# STice.net
KiCad netlist of a schematic drawn in Altium Designer
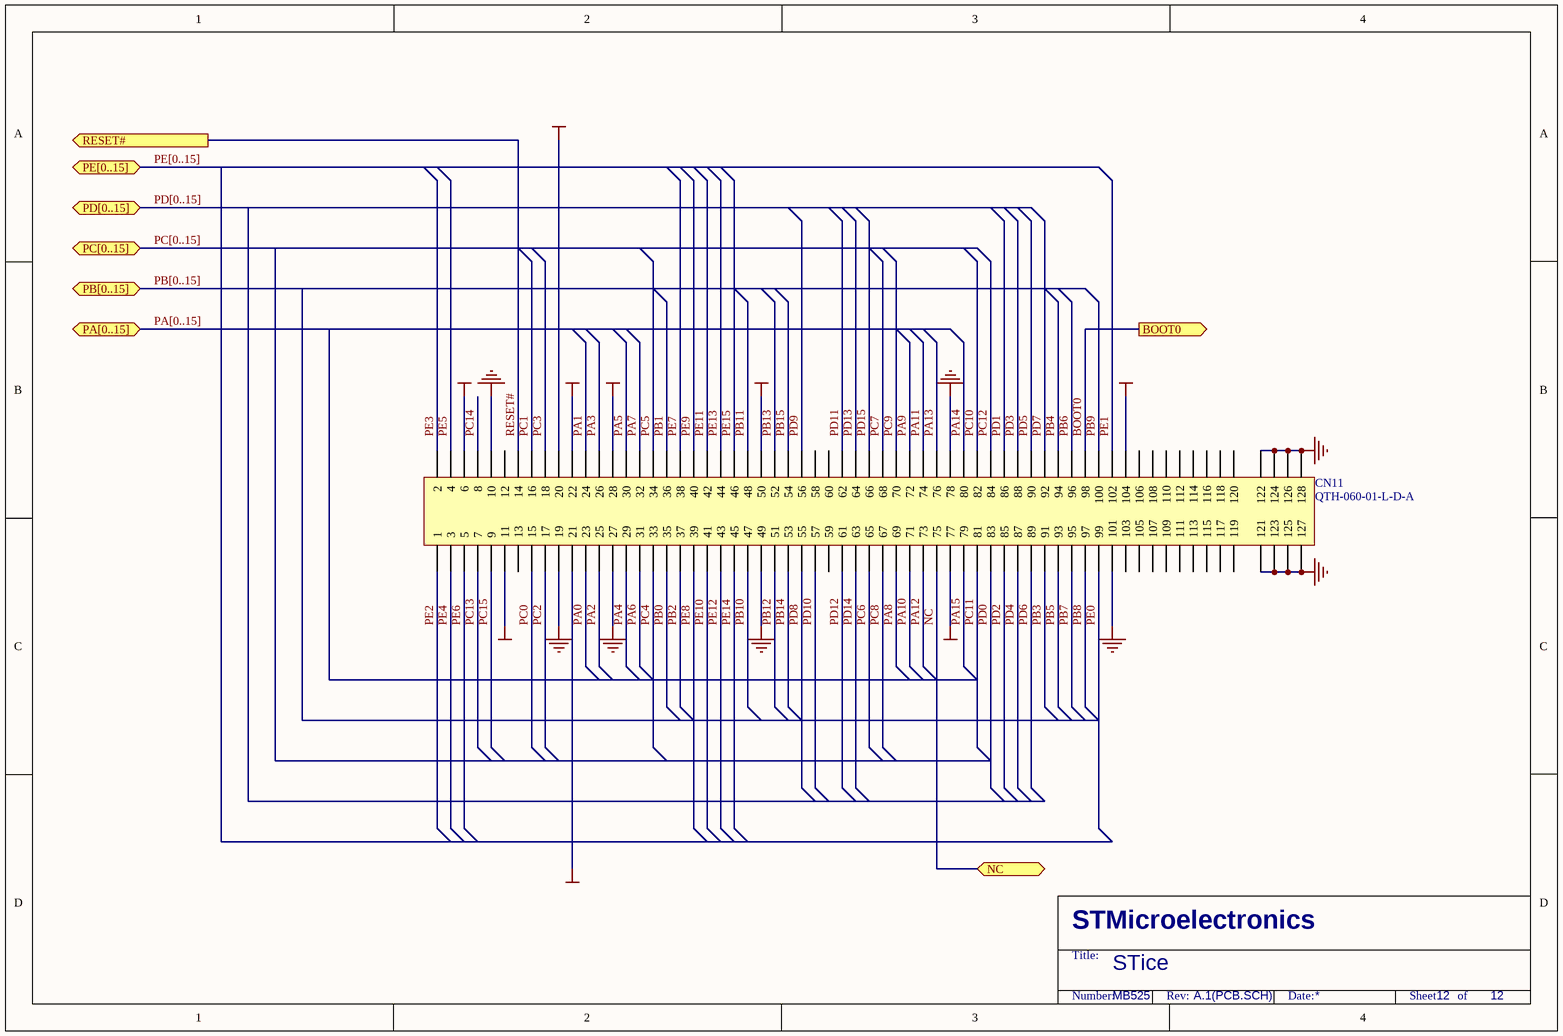
[diagram p0: STice.SchDoc]

(export (version "E")
  (design (tool "Eeschema 10.0.6"))
  (components
    (comp (ref "CN11")
      (value "QTH-060-01-L-D-A")
      (footprint "QTH-060-01-L-D-A")
      (libsource (lib "MB525") (part "QTH-060-01-L-D-A"))
    )
  )
  (nets
    (net (code "1") (name "/BOOT0") (class "Default")
      (node (ref "CN11") (pin "98") (pinfunction "98_98") (pintype "passive"))
    )
    (net (code "2") (name "/NC") (class "Default")
      (node (ref "CN11") (pin "75") (pinfunction "75_75") (pintype "passive"))
    )
    (net (code "3") (name "/PA0") (class "Default")
      (node (ref "CN11") (pin "23") (pinfunction "23_23") (pintype "passive"))
    )
    (net (code "4") (name "/PA1") (class "Default")
      (node (ref "CN11") (pin "24") (pinfunction "24_24") (pintype "passive"))
    )
    (net (code "5") (name "/PA2") (class "Default")
      (node (ref "CN11") (pin "25") (pinfunction "25_25") (pintype "passive"))
    )
    (net (code "6") (name "/PA3") (class "Default")
      (node (ref "CN11") (pin "26") (pinfunction "26_26") (pintype "passive"))
    )
    (net (code "7") (name "/PA4") (class "Default")
      (node (ref "CN11") (pin "29") (pinfunction "29_29") (pintype "passive"))
    )
    (net (code "8") (name "/PA5") (class "Default")
      (node (ref "CN11") (pin "30") (pinfunction "30_30") (pintype "passive"))
    )
    (net (code "9") (name "/PA6") (class "Default")
      (node (ref "CN11") (pin "31") (pinfunction "31_31") (pintype "passive"))
    )
    (net (code "10") (name "/PA7") (class "Default")
      (node (ref "CN11") (pin "32") (pinfunction "32_32") (pintype "passive"))
    )
    (net (code "11") (name "/PA8") (class "Default")
      (node (ref "CN11") (pin "69") (pinfunction "69_69") (pintype "passive"))
    )
    (net (code "12") (name "/PA9") (class "Default")
      (node (ref "CN11") (pin "72") (pinfunction "72_72") (pintype "passive"))
    )
    (net (code "13") (name "/PA10") (class "Default")
      (node (ref "CN11") (pin "71") (pinfunction "71_71") (pintype "passive"))
    )
    (net (code "14") (name "/PA11") (class "Default")
      (node (ref "CN11") (pin "74") (pinfunction "74_74") (pintype "passive"))
    )
    (net (code "15") (name "/PA12") (class "Default")
      (node (ref "CN11") (pin "73") (pinfunction "73_73") (pintype "passive"))
    )
    (net (code "16") (name "/PA13") (class "Default")
      (node (ref "CN11") (pin "76") (pinfunction "76_76") (pintype "passive"))
    )
    (net (code "17") (name "/PA14") (class "Default")
      (node (ref "CN11") (pin "80") (pinfunction "80_80") (pintype "passive"))
    )
    (net (code "18") (name "/PA15") (class "Default")
      (node (ref "CN11") (pin "79") (pinfunction "79_79") (pintype "passive"))
    )
    (net (code "20") (name "/PB0") (class "Default")
      (node (ref "CN11") (pin "35") (pinfunction "35_35") (pintype "passive"))
    )
    (net (code "21") (name "/PB1") (class "Default")
      (node (ref "CN11") (pin "36") (pinfunction "36_36") (pintype "passive"))
    )
    (net (code "22") (name "/PB2") (class "Default")
      (node (ref "CN11") (pin "37") (pinfunction "37_37") (pintype "passive"))
    )
    (net (code "23") (name "/PB3") (class "Default")
      (node (ref "CN11") (pin "91") (pinfunction "91_91") (pintype "passive"))
    )
    (net (code "24") (name "/PB4") (class "Default")
      (node (ref "CN11") (pin "94") (pinfunction "94_94") (pintype "passive"))
    )
    (net (code "25") (name "/PB5") (class "Default")
      (node (ref "CN11") (pin "93") (pinfunction "93_93") (pintype "passive"))
    )
    (net (code "26") (name "/PB6") (class "Default")
      (node (ref "CN11") (pin "96") (pinfunction "96_96") (pintype "passive"))
    )
    (net (code "27") (name "/PB7") (class "Default")
      (node (ref "CN11") (pin "95") (pinfunction "95_95") (pintype "passive"))
    )
    (net (code "28") (name "/PB8") (class "Default")
      (node (ref "CN11") (pin "97") (pinfunction "97_97") (pintype "passive"))
    )
    (net (code "29") (name "/PB9") (class "Default")
      (node (ref "CN11") (pin "100") (pinfunction "100_100") (pintype "passive"))
    )
    (net (code "30") (name "/PB10") (class "Default")
      (node (ref "CN11") (pin "47") (pinfunction "47_47") (pintype "passive"))
    )
    (net (code "31") (name "/PB11") (class "Default")
      (node (ref "CN11") (pin "48") (pinfunction "48_48") (pintype "passive"))
    )
    (net (code "32") (name "/PB12") (class "Default")
      (node (ref "CN11") (pin "51") (pinfunction "51_51") (pintype "passive"))
    )
    (net (code "33") (name "/PB13") (class "Default")
      (node (ref "CN11") (pin "52") (pinfunction "52_52") (pintype "passive"))
    )
    (net (code "34") (name "/PB14") (class "Default")
      (node (ref "CN11") (pin "53") (pinfunction "53_53") (pintype "passive"))
    )
    (net (code "35") (name "/PB15") (class "Default")
      (node (ref "CN11") (pin "54") (pinfunction "54_54") (pintype "passive"))
    )
    (net (code "37") (name "/PC0") (class "Default")
      (node (ref "CN11") (pin "15") (pinfunction "15_15") (pintype "passive"))
    )
    (net (code "38") (name "/PC1") (class "Default")
      (node (ref "CN11") (pin "16") (pinfunction "16_16") (pintype "passive"))
    )
    (net (code "39") (name "/PC2") (class "Default")
      (node (ref "CN11") (pin "17") (pinfunction "17_17") (pintype "passive"))
    )
    (net (code "40") (name "/PC3") (class "Default")
      (node (ref "CN11") (pin "18") (pinfunction "18_18") (pintype "passive"))
    )
    (net (code "41") (name "/PC4") (class "Default")
      (node (ref "CN11") (pin "33") (pinfunction "33_33") (pintype "passive"))
    )
    (net (code "42") (name "/PC5") (class "Default")
      (node (ref "CN11") (pin "34") (pinfunction "34_34") (pintype "passive"))
    )
    (net (code "43") (name "/PC6") (class "Default")
      (node (ref "CN11") (pin "65") (pinfunction "65_65") (pintype "passive"))
    )
    (net (code "44") (name "/PC7") (class "Default")
      (node (ref "CN11") (pin "68") (pinfunction "68_68") (pintype "passive"))
    )
    (net (code "45") (name "/PC8") (class "Default")
      (node (ref "CN11") (pin "67") (pinfunction "67_67") (pintype "passive"))
    )
    (net (code "46") (name "/PC9") (class "Default")
      (node (ref "CN11") (pin "70") (pinfunction "70_70") (pintype "passive"))
    )
    (net (code "47") (name "/PC10") (class "Default")
      (node (ref "CN11") (pin "82") (pinfunction "82_82") (pintype "passive"))
    )
    (net (code "48") (name "/PC11") (class "Default")
      (node (ref "CN11") (pin "81") (pinfunction "81_81") (pintype "passive"))
    )
    (net (code "49") (name "/PC12") (class "Default")
      (node (ref "CN11") (pin "84") (pinfunction "84_84") (pintype "passive"))
    )
    (net (code "50") (name "/PC13") (class "Default")
      (node (ref "CN11") (pin "7") (pinfunction "7_7") (pintype "passive"))
    )
    (net (code "51") (name "/PC14") (class "Default")
      (node (ref "CN11") (pin "8") (pinfunction "8_8") (pintype "passive"))
    )
    (net (code "52") (name "/PC15") (class "Default")
      (node (ref "CN11") (pin "9") (pinfunction "9_9") (pintype "passive"))
    )
    (net (code "54") (name "/PD0") (class "Default")
      (node (ref "CN11") (pin "83") (pinfunction "83_83") (pintype "passive"))
    )
    (net (code "55") (name "/PD1") (class "Default")
      (node (ref "CN11") (pin "86") (pinfunction "86_86") (pintype "passive"))
    )
    (net (code "56") (name "/PD2") (class "Default")
      (node (ref "CN11") (pin "85") (pinfunction "85_85") (pintype "passive"))
    )
    (net (code "57") (name "/PD3") (class "Default")
      (node (ref "CN11") (pin "88") (pinfunction "88_88") (pintype "passive"))
    )
    (net (code "58") (name "/PD4") (class "Default")
      (node (ref "CN11") (pin "87") (pinfunction "87_87") (pintype "passive"))
    )
    (net (code "59") (name "/PD5") (class "Default")
      (node (ref "CN11") (pin "90") (pinfunction "90_90") (pintype "passive"))
    )
    (net (code "60") (name "/PD6") (class "Default")
      (node (ref "CN11") (pin "89") (pinfunction "89_89") (pintype "passive"))
    )
    (net (code "61") (name "/PD7") (class "Default")
      (node (ref "CN11") (pin "92") (pinfunction "92_92") (pintype "passive"))
    )
    (net (code "62") (name "/PD8") (class "Default")
      (node (ref "CN11") (pin "55") (pinfunction "55_55") (pintype "passive"))
    )
    (net (code "63") (name "/PD9") (class "Default")
      (node (ref "CN11") (pin "56") (pinfunction "56_56") (pintype "passive"))
    )
    (net (code "64") (name "/PD10") (class "Default")
      (node (ref "CN11") (pin "57") (pinfunction "57_57") (pintype "passive"))
    )
    (net (code "65") (name "/PD11") (class "Default")
      (node (ref "CN11") (pin "62") (pinfunction "62_62") (pintype "passive"))
    )
    (net (code "66") (name "/PD12") (class "Default")
      (node (ref "CN11") (pin "61") (pinfunction "61_61") (pintype "passive"))
    )
    (net (code "67") (name "/PD13") (class "Default")
      (node (ref "CN11") (pin "64") (pinfunction "64_64") (pintype "passive"))
    )
    (net (code "68") (name "/PD14") (class "Default")
      (node (ref "CN11") (pin "63") (pinfunction "63_63") (pintype "passive"))
    )
    (net (code "69") (name "/PD15") (class "Default")
      (node (ref "CN11") (pin "66") (pinfunction "66_66") (pintype "passive"))
    )
    (net (code "71") (name "/PE0") (class "Default")
      (node (ref "CN11") (pin "99") (pinfunction "99_99") (pintype "passive"))
    )
    (net (code "72") (name "/PE1") (class "Default")
      (node (ref "CN11") (pin "102") (pinfunction "102_102") (pintype "passive"))
    )
    (net (code "73") (name "/PE2") (class "Default")
      (node (ref "CN11") (pin "1") (pinfunction "1_1") (pintype "passive"))
    )
    (net (code "74") (name "/PE3") (class "Default")
      (node (ref "CN11") (pin "2") (pinfunction "2_2") (pintype "passive"))
    )
    (net (code "75") (name "/PE4") (class "Default")
      (node (ref "CN11") (pin "3") (pinfunction "3_3") (pintype "passive"))
    )
    (net (code "76") (name "/PE5") (class "Default")
      (node (ref "CN11") (pin "4") (pinfunction "4_4") (pintype "passive"))
    )
    (net (code "77") (name "/PE6") (class "Default")
      (node (ref "CN11") (pin "5") (pinfunction "5_5") (pintype "passive"))
    )
    (net (code "78") (name "/PE7") (class "Default")
      (node (ref "CN11") (pin "38") (pinfunction "38_38") (pintype "passive"))
    )
    (net (code "79") (name "/PE8") (class "Default")
      (node (ref "CN11") (pin "39") (pinfunction "39_39") (pintype "passive"))
    )
    (net (code "80") (name "/PE9") (class "Default")
      (node (ref "CN11") (pin "40") (pinfunction "40_40") (pintype "passive"))
    )
    (net (code "81") (name "/PE10") (class "Default")
      (node (ref "CN11") (pin "41") (pinfunction "41_41") (pintype "passive"))
    )
    (net (code "82") (name "/PE11") (class "Default")
      (node (ref "CN11") (pin "42") (pinfunction "42_42") (pintype "passive"))
    )
    (net (code "83") (name "/PE12") (class "Default")
      (node (ref "CN11") (pin "43") (pinfunction "43_43") (pintype "passive"))
    )
    (net (code "84") (name "/PE13") (class "Default")
      (node (ref "CN11") (pin "44") (pinfunction "44_44") (pintype "passive"))
    )
    (net (code "85") (name "/PE14") (class "Default")
      (node (ref "CN11") (pin "45") (pinfunction "45_45") (pintype "passive"))
    )
    (net (code "86") (name "/PE15") (class "Default")
      (node (ref "CN11") (pin "46") (pinfunction "46_46") (pintype "passive"))
    )
    (net (code "88") (name "/RESET#") (class "Default")
      (node (ref "CN11") (pin "14") (pinfunction "14_14") (pintype "passive"))
    )
    (net (code "89") (name "GND") (class "Default")
      (node (ref "CN11") (pin "10") (pinfunction "10_10") (pintype "passive"))
      (node (ref "CN11") (pin "101") (pinfunction "101_101") (pintype "passive"))
      (node (ref "CN11") (pin "121") (pinfunction "121_121") (pintype "passive"))
      (node (ref "CN11") (pin "122") (pinfunction "122_122") (pintype "passive"))
      (node (ref "CN11") (pin "123") (pinfunction "123_123") (pintype "passive"))
      (node (ref "CN11") (pin "124") (pinfunction "124_124") (pintype "passive"))
      (node (ref "CN11") (pin "125") (pinfunction "125_125") (pintype "passive"))
      (node (ref "CN11") (pin "126") (pinfunction "126_126") (pintype "passive"))
      (node (ref "CN11") (pin "127") (pinfunction "127_127") (pintype "passive"))
      (node (ref "CN11") (pin "128") (pinfunction "128_128") (pintype "passive"))
      (node (ref "CN11") (pin "19") (pinfunction "19_19") (pintype "passive"))
      (node (ref "CN11") (pin "27") (pinfunction "27_27") (pintype "passive"))
      (node (ref "CN11") (pin "49") (pinfunction "49_49") (pintype "passive"))
      (node (ref "CN11") (pin "78") (pinfunction "78_78") (pintype "passive"))
    )
    (net (code "90") (name "VDD") (class "Default")
      (node (ref "CN11") (pin "104") (pinfunction "104_104") (pintype "passive"))
      (node (ref "CN11") (pin "11") (pinfunction "11_11") (pintype "passive"))
      (node (ref "CN11") (pin "28") (pinfunction "28_28") (pintype "passive"))
      (node (ref "CN11") (pin "50") (pinfunction "50_50") (pintype "passive"))
      (node (ref "CN11") (pin "77") (pinfunction "77_77") (pintype "passive"))
    )
    (net (code "91") (name "VDDA") (class "Default")
      (node (ref "CN11") (pin "22") (pinfunction "22_22") (pintype "passive"))
    )
    (net (code "92") (name "VREF+") (class "Default")
      (node (ref "CN11") (pin "21") (pinfunction "21_21") (pintype "passive"))
    )
    (net (code "93") (name "VREF-") (class "Default")
      (node (ref "CN11") (pin "20") (pinfunction "20_20") (pintype "passive"))
    )
    (net (code "94") (name "Vbat") (class "Default")
      (node (ref "CN11") (pin "6") (pinfunction "6_6") (pintype "passive"))
    )
    (net (code "95") (name "unconnected-(CN11-Pad12)") (class "Default")
      (node (ref "CN11") (pin "12") (pinfunction "12_12") (pintype "passive"))
    )
    (net (code "96") (name "unconnected-(CN11-Pad13)") (class "Default")
      (node (ref "CN11") (pin "13") (pinfunction "13_13") (pintype "passive"))
    )
    (net (code "97") (name "unconnected-(CN11-Pad58)") (class "Default")
      (node (ref "CN11") (pin "58") (pinfunction "58_58") (pintype "passive"))
    )
    (net (code "98") (name "unconnected-(CN11-Pad59)") (class "Default")
      (node (ref "CN11") (pin "59") (pinfunction "59_59") (pintype "passive"))
    )
    (net (code "99") (name "unconnected-(CN11-Pad60)") (class "Default")
      (node (ref "CN11") (pin "60") (pinfunction "60_60") (pintype "passive"))
    )
    (net (code "100") (name "unconnected-(CN11-Pad103)") (class "Default")
      (node (ref "CN11") (pin "103") (pinfunction "103_103") (pintype "passive"))
    )
    (net (code "101") (name "unconnected-(CN11-Pad105)") (class "Default")
      (node (ref "CN11") (pin "105") (pinfunction "105_105") (pintype "passive"))
    )
    (net (code "102") (name "unconnected-(CN11-Pad106)") (class "Default")
      (node (ref "CN11") (pin "106") (pinfunction "106_106") (pintype "passive"))
    )
    (net (code "103") (name "unconnected-(CN11-Pad107)") (class "Default")
      (node (ref "CN11") (pin "107") (pinfunction "107_107") (pintype "passive"))
    )
    (net (code "104") (name "unconnected-(CN11-Pad108)") (class "Default")
      (node (ref "CN11") (pin "108") (pinfunction "108_108") (pintype "passive"))
    )
    (net (code "105") (name "unconnected-(CN11-Pad109)") (class "Default")
      (node (ref "CN11") (pin "109") (pinfunction "109_109") (pintype "passive"))
    )
    (net (code "106") (name "unconnected-(CN11-Pad110)") (class "Default")
      (node (ref "CN11") (pin "110") (pinfunction "110_110") (pintype "passive"))
    )
    (net (code "107") (name "unconnected-(CN11-Pad111)") (class "Default")
      (node (ref "CN11") (pin "111") (pinfunction "111_111") (pintype "passive"))
    )
    (net (code "108") (name "unconnected-(CN11-Pad112)") (class "Default")
      (node (ref "CN11") (pin "112") (pinfunction "112_112") (pintype "passive"))
    )
    (net (code "109") (name "unconnected-(CN11-Pad113)") (class "Default")
      (node (ref "CN11") (pin "113") (pinfunction "113_113") (pintype "passive"))
    )
    (net (code "110") (name "unconnected-(CN11-Pad114)") (class "Default")
      (node (ref "CN11") (pin "114") (pinfunction "114_114") (pintype "passive"))
    )
    (net (code "111") (name "unconnected-(CN11-Pad115)") (class "Default")
      (node (ref "CN11") (pin "115") (pinfunction "115_115") (pintype "passive"))
    )
    (net (code "112") (name "unconnected-(CN11-Pad116)") (class "Default")
      (node (ref "CN11") (pin "116") (pinfunction "116_116") (pintype "passive"))
    )
    (net (code "113") (name "unconnected-(CN11-Pad117)") (class "Default")
      (node (ref "CN11") (pin "117") (pinfunction "117_117") (pintype "passive"))
    )
    (net (code "114") (name "unconnected-(CN11-Pad118)") (class "Default")
      (node (ref "CN11") (pin "118") (pinfunction "118_118") (pintype "passive"))
    )
    (net (code "115") (name "unconnected-(CN11-Pad119)") (class "Default")
      (node (ref "CN11") (pin "119") (pinfunction "119_119") (pintype "passive"))
    )
    (net (code "116") (name "unconnected-(CN11-Pad120)") (class "Default")
      (node (ref "CN11") (pin "120") (pinfunction "120_120") (pintype "passive"))
    )
  )
)
